# TopLevelBlock.net
KiCad netlist of a schematic drawn in Altium Designer
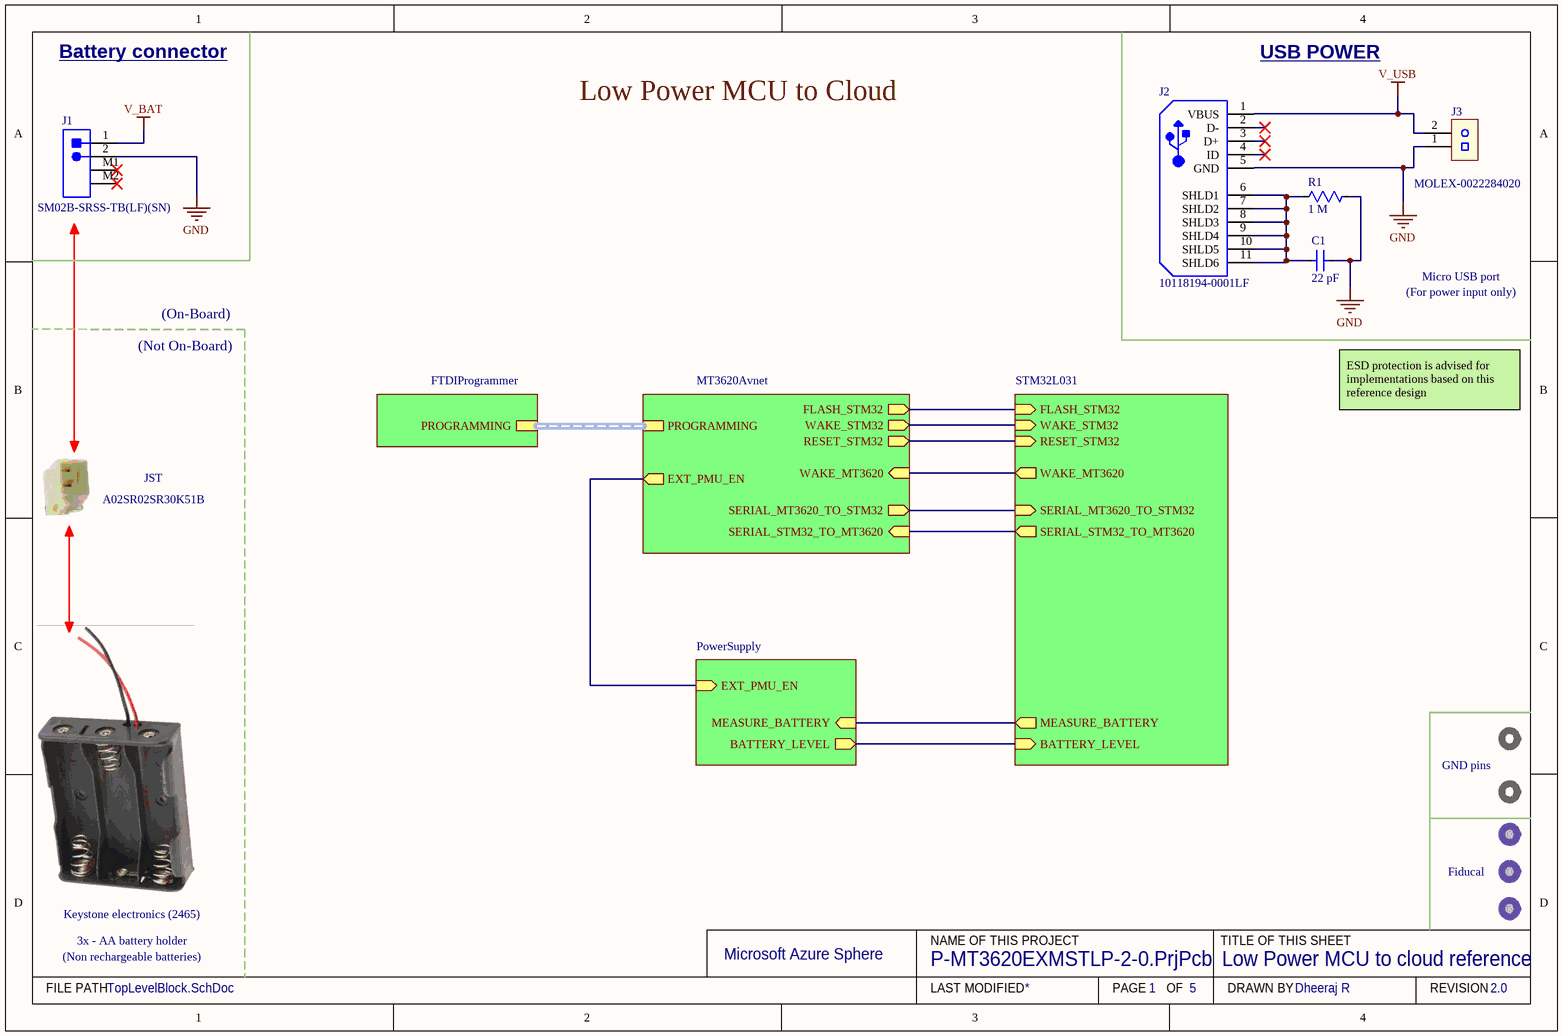
[diagram p0: TopLevelBlock.SchDoc]

(export (version "E")
  (design (tool "Eeschema 10.0.6"))
  (components
    (comp (ref "C1")
      (value "22 pF")
      (footprint "CC0603")
      (description "22PF 0603 100V C0G/NPO")
      (fields
        (field (name "MANUFACTURER") "Yageo")
        (field (name "MANUFACTURER PART NUMBER") "CC0603JRNPO0BN220")
      )
      (libsource (lib "Yageo") (part "CC0603JRNPO0BN220"))
    )
    (comp (ref "J1")
      (value "SM02B-SRSS-TB(LF)(SN)")
      (footprint "SM02B-SRSS-TB")
      (description "Conn Shrouded Header HDR 2 POS 1mm Solder RA SMD T/R")
      (fields (field (name "MANUFACTURER") "JST"))
      (libsource (lib "JST") (part "SM02B-SRSS-TB(LF)(SN)"))
    )
    (comp (ref "J2")
      (value "Amphenol FCI 10118194-0001LF")
      (footprint "FCI-10118194-0001LF-5_V no slots")
      (description "CONN USB MICRO B RECPT SMT R/A")
      (fields
        (field (name "MANUFACTURER") "Amphenol FCI")
        (field (name "MANUFACTURER PART NUMBER") "10118194-0001LF")
        (field (name "CREATED BY") "HUGHWI")
      )
      (libsource (lib "Amphenol") (part "Amphenol FCI 10118194-0001LF"))
    )
    (comp (ref "J3")
      (value "MOLEX-0022284020")
      (footprint "0022284020")
      (description "CONN HEADER 2POS .100 VERT TIN")
      (fields
        (field (name "MANUFACTURER") "Molex, LLC")
        (field (name "MANUFACTURER PART NUMBER") "0022284020")
      )
      (libsource (lib "Molex") (part "MOLEX-0022284020"))
    )
    (comp (ref "R1")
      (value "1 M")
      (footprint "RC0603")
      (description "1M 0603 Case 1% 0.1W 100ppm/C")
      (fields
        (field (name "MANUFACTURER") "Yageo")
        (field (name "MANUFACTURER PART NUMBER") "RC0603FR-071ML")
      )
      (libsource (lib "Yageo") (part "RC0603FR-071ML"))
    )
  )
  (nets
    (net (code "11") (name "GND") (class "Default")
      (node (ref "C1") (pin "2") (pinfunction "2_2") (pintype "passive"))
      (node (ref "J1") (pin "2") (pinfunction "2_2") (pintype "passive"))
      (node (ref "J2") (pin "5") (pinfunction "GND_5") (pintype "passive"))
      (node (ref "J3") (pin "1") (pinfunction "1_1") (pintype "passive"))
      (node (ref "R1") (pin "1") (pinfunction "1_1") (pintype "passive"))
    )
    (net (code "12") (name "Net-(J2-SHLD1)") (class "Default")
      (node (ref "C1") (pin "1") (pinfunction "1_1") (pintype "passive"))
      (node (ref "J2") (pin "10") (pinfunction "SHLD5_10") (pintype "passive"))
      (node (ref "J2") (pin "11") (pinfunction "SHLD6_11") (pintype "passive"))
      (node (ref "J2") (pin "6") (pinfunction "SHLD1_6") (pintype "passive"))
      (node (ref "J2") (pin "7") (pinfunction "SHLD2_7") (pintype "passive"))
      (node (ref "J2") (pin "8") (pinfunction "SHLD3_8") (pintype "passive"))
      (node (ref "J2") (pin "9") (pinfunction "SHLD4_9") (pintype "passive"))
      (node (ref "R1") (pin "2") (pinfunction "2_2") (pintype "passive"))
    )
    (net (code "13") (name "V_BAT") (class "Default")
      (node (ref "J1") (pin "1") (pinfunction "1_1") (pintype "passive"))
    )
    (net (code "14") (name "V_USB") (class "Default")
      (node (ref "J2") (pin "1") (pinfunction "VBUS_1") (pintype "passive"))
      (node (ref "J3") (pin "2") (pinfunction "2_2") (pintype "passive"))
    )
    (net (code "15") (name "unconnected-(J1-PadM1)") (class "Default")
      (node (ref "J1") (pin "M1") (pinfunction "M1_M1") (pintype "passive+no_connect"))
    )
    (net (code "16") (name "unconnected-(J1-PadM2)") (class "Default")
      (node (ref "J1") (pin "M2") (pinfunction "M2_M2") (pintype "passive+no_connect"))
    )
    (net (code "17") (name "unconnected-(J2-D+-Pad3)") (class "Default")
      (node (ref "J2") (pin "3") (pinfunction "D+_3") (pintype "passive+no_connect"))
    )
    (net (code "18") (name "unconnected-(J2-D--Pad2)") (class "Default")
      (node (ref "J2") (pin "2") (pinfunction "D-_2") (pintype "passive+no_connect"))
    )
    (net (code "19") (name "unconnected-(J2-ID-Pad4)") (class "Default")
      (node (ref "J2") (pin "4") (pinfunction "ID_4") (pintype "passive+no_connect"))
    )
  )
)
